# bat_mini7.net
KiCad netlist of a schematic drawn in EAGLE
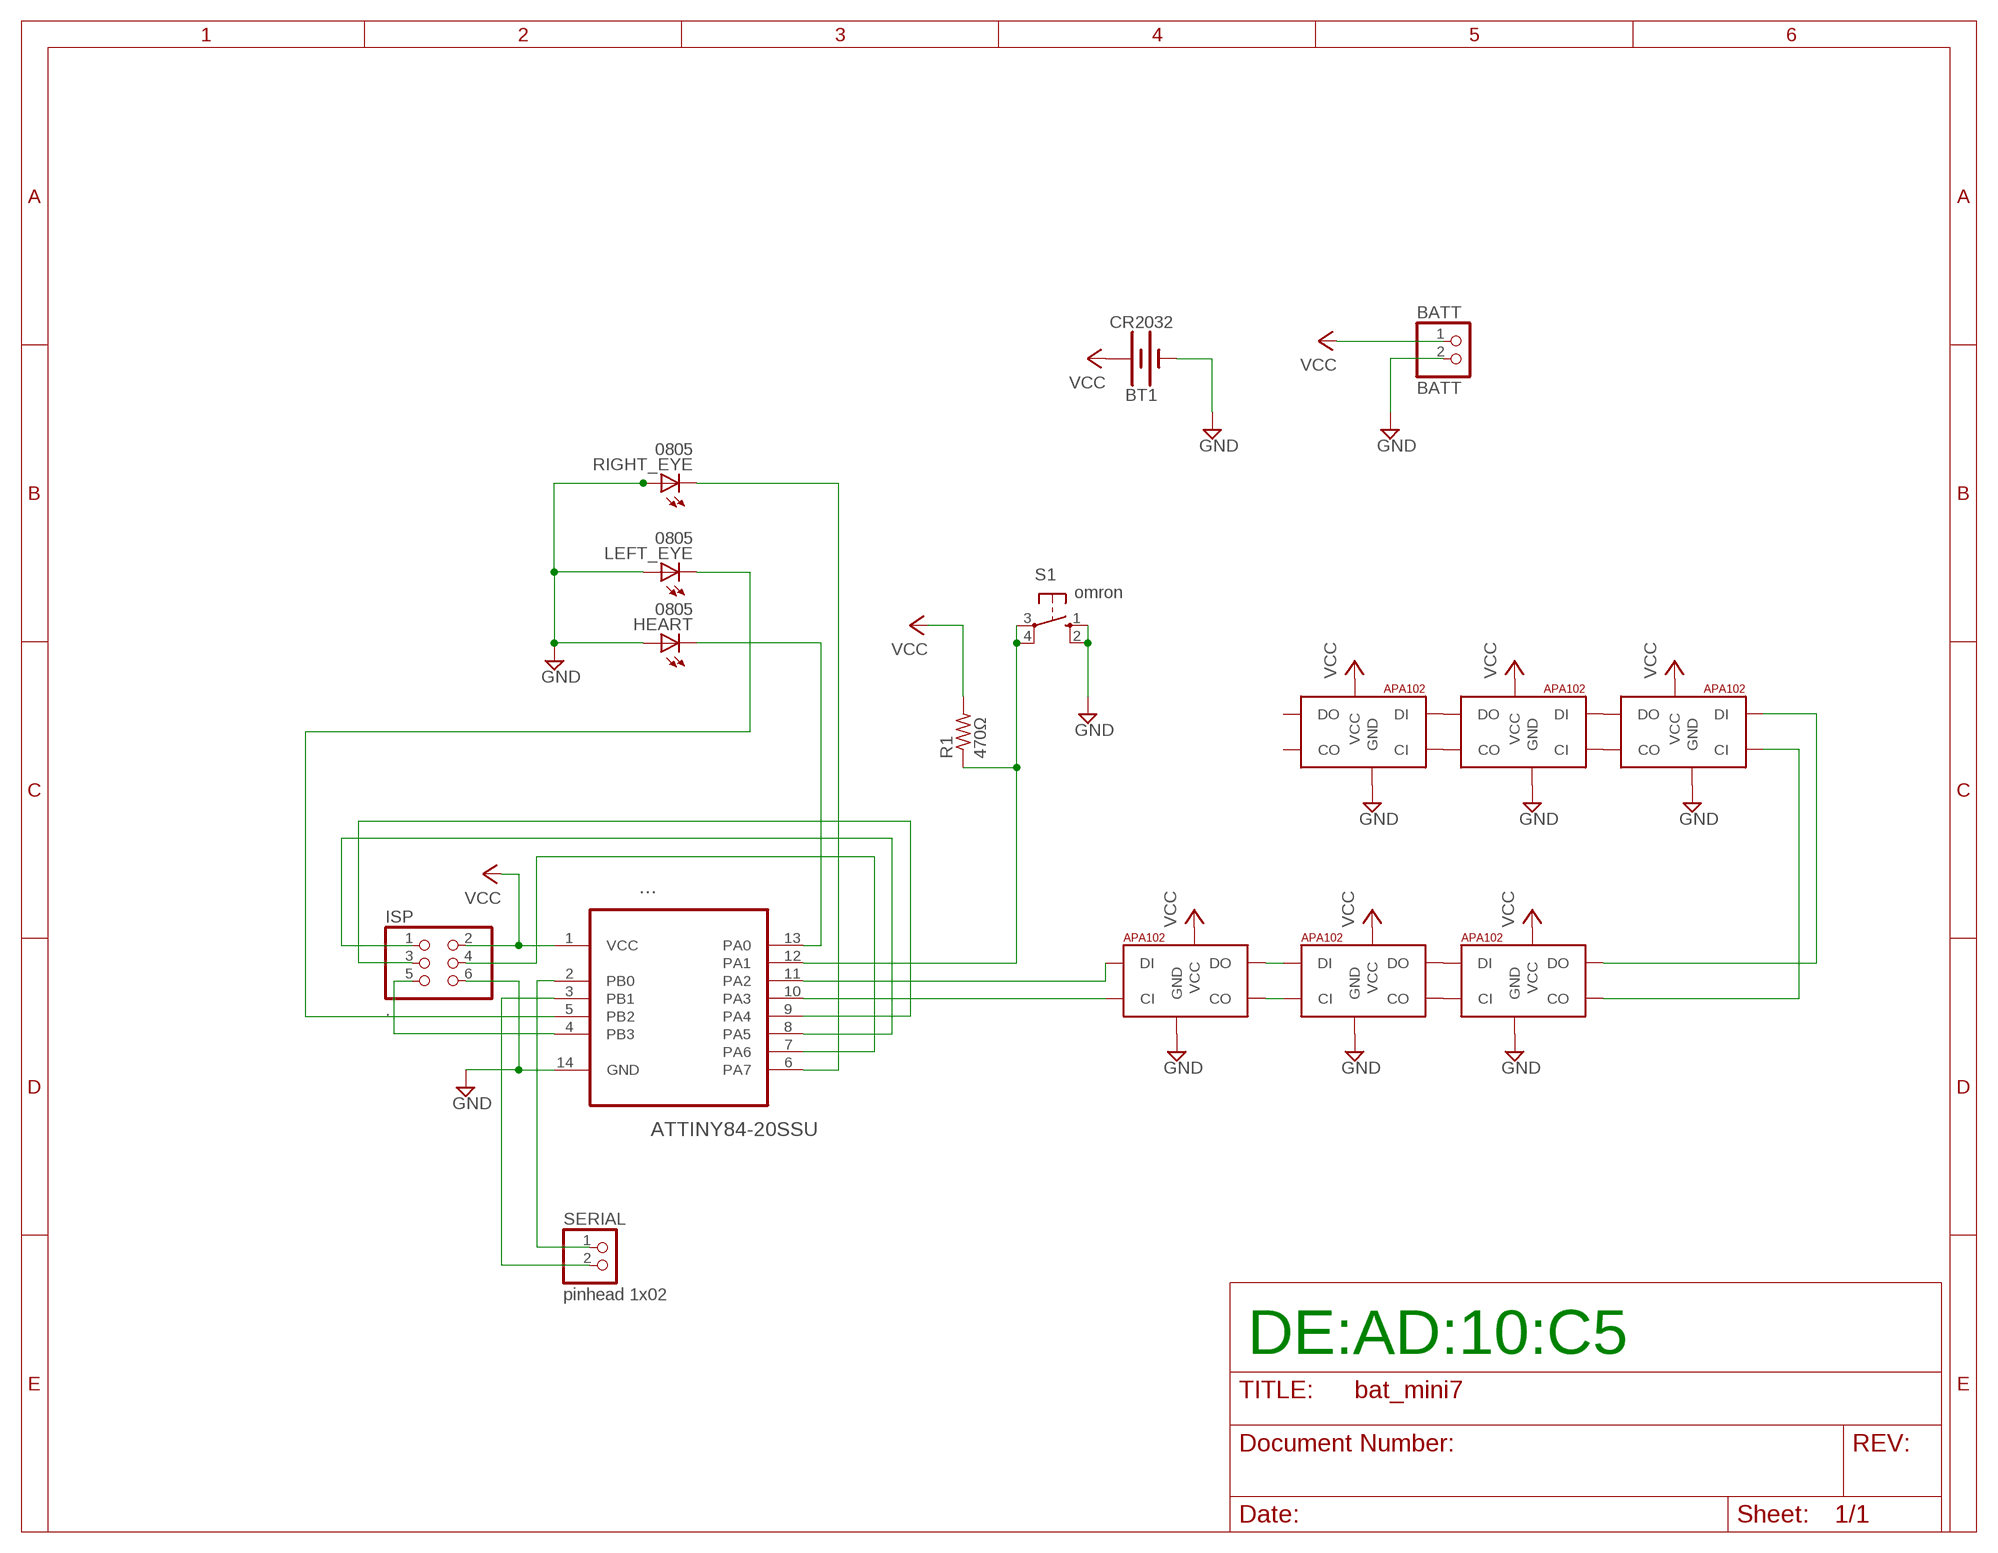
[diagram p0: schematic, sheet 1]

(export (version "E")
  (design (tool "Eeschema 10.0.6"))
  (components
    (comp (ref "...")
      (value "ATTINY84-20SSU")
      (footprint "eagle-import:SOIC127P600X175-14N")
      (libsource (lib "eagle-import") (part "ATTINY84-20SSU"))
    )
    (comp (ref "BATT")
      (value "BATT")
      (footprint "eagle-import:1X02")
      (libsource (lib "eagle-import") (part "PINHD-1X2"))
    )
    (comp (ref "BT1")
      (value "CR2032")
      (footprint "eagle-import:BATTCON_20MM_4LEGS")
      (libsource (lib "eagle-import") (part "BATTERY-20MM_SMD_4LEGS"))
    )
    (comp (ref "HEART")
      (value "0805")
      (footprint "eagle-import:CHIP-LED0805")
      (libsource (lib "eagle-import") (part "LEDCHIP-LED0805"))
    )
    (comp (ref "ISP")
      (value ".")
      (footprint "eagle-import:2X03")
      (libsource (lib "eagle-import") (part "PINHD-2X3"))
    )
    (comp (ref "LEFT_EYE")
      (value "0805")
      (footprint "eagle-import:CHIP-LED0805")
      (libsource (lib "eagle-import") (part "LEDCHIP-LED0805"))
    )
    (comp (ref "R1")
      (value "470Ω")
      (footprint "eagle-import:R0805")
      (libsource (lib "eagle-import") (part "R-US_R0805"))
    )
    (comp (ref "RIGHT_EYE")
      (value "0805")
      (footprint "eagle-import:CHIP-LED0805")
      (libsource (lib "eagle-import") (part "LEDCHIP-LED0805"))
    )
    (comp (ref "S1")
      (value "omron")
      (footprint "eagle-import:B3F-10XX")
      (fields (field (name "MPN") "B3F-1000"))
      (libsource (lib "eagle-import") (part "10-XX"))
    )
    (comp (ref "SERIAL")
      (value "pinhead 1x02")
      (footprint "eagle-import:1X02")
      (libsource (lib "eagle-import") (part "PINHD-1X2"))
    )
    (comp (ref "U$1")
      (value "APA1025050")
      (footprint "eagle-import:APA102_5050")
      (libsource (lib "eagle-import") (part "APA1025050"))
    )
    (comp (ref "U$2")
      (value "APA1025050")
      (footprint "eagle-import:APA102_5050")
      (libsource (lib "eagle-import") (part "APA1025050"))
    )
    (comp (ref "U$3")
      (value "APA1025050")
      (footprint "eagle-import:APA102_5050")
      (libsource (lib "eagle-import") (part "APA1025050"))
    )
    (comp (ref "U$5")
      (value "APA1025050")
      (footprint "eagle-import:APA102_5050")
      (libsource (lib "eagle-import") (part "APA1025050"))
    )
    (comp (ref "U$6")
      (value "APA1025050")
      (footprint "eagle-import:APA102_5050")
      (libsource (lib "eagle-import") (part "APA1025050"))
    )
    (comp (ref "U$7")
      (value "APA1025050")
      (footprint "eagle-import:APA102_5050")
      (libsource (lib "eagle-import") (part "APA1025050"))
    )
  )
  (nets
    (net (code "1") (name "GND") (class "Default")
      (node (ref "...") (pin "14") (pinfunction "GND_14") (pintype "passive"))
      (node (ref "BATT") (pin "2") (pinfunction "2_2") (pintype "passive"))
      (node (ref "BT1") (pin "NEGATIVE") (pinfunction "-_NEGATIVE") (pintype "power_in"))
      (node (ref "HEART") (pin "A") (pinfunction "A_A") (pintype "passive"))
      (node (ref "ISP") (pin "6") (pinfunction "6_6") (pintype "passive"))
      (node (ref "LEFT_EYE") (pin "A") (pinfunction "A_A") (pintype "passive"))
      (node (ref "RIGHT_EYE") (pin "A") (pinfunction "A_A") (pintype "passive"))
      (node (ref "S1") (pin "1") (pinfunction "S_1") (pintype "passive"))
      (node (ref "S1") (pin "2") (pinfunction "S1_2") (pintype "passive"))
      (node (ref "U$1") (pin "6") (pinfunction "GND_6") (pintype "bidirectional"))
      (node (ref "U$2") (pin "6") (pinfunction "GND_6") (pintype "bidirectional"))
      (node (ref "U$3") (pin "6") (pinfunction "GND_6") (pintype "bidirectional"))
      (node (ref "U$5") (pin "6") (pinfunction "GND_6") (pintype "bidirectional"))
      (node (ref "U$6") (pin "6") (pinfunction "GND_6") (pintype "bidirectional"))
      (node (ref "U$7") (pin "6") (pinfunction "GND_6") (pintype "bidirectional"))
    )
    (net (code "2") (name "Net-(...-PA0)") (class "Default")
      (node (ref "...") (pin "13") (pinfunction "PA0_13") (pintype "bidirectional"))
      (node (ref "HEART") (pin "C") (pinfunction "C_C") (pintype "passive"))
    )
    (net (code "3") (name "Net-(...-PA1)") (class "Default")
      (node (ref "...") (pin "12") (pinfunction "PA1_12") (pintype "bidirectional"))
      (node (ref "R1") (pin "1") (pinfunction "1_1") (pintype "passive"))
      (node (ref "S1") (pin "3") (pinfunction "P_3") (pintype "passive"))
      (node (ref "S1") (pin "4") (pinfunction "P1_4") (pintype "passive"))
    )
    (net (code "4") (name "Net-(...-PA2)") (class "Default")
      (node (ref "...") (pin "11") (pinfunction "PA2_11") (pintype "bidirectional"))
      (node (ref "U$1") (pin "4") (pinfunction "DI_4") (pintype "bidirectional"))
    )
    (net (code "5") (name "Net-(...-PA3)") (class "Default")
      (node (ref "...") (pin "10") (pinfunction "PA3_10") (pintype "bidirectional"))
      (node (ref "U$1") (pin "5") (pinfunction "CI_5") (pintype "bidirectional"))
    )
    (net (code "6") (name "Net-(...-PA4)") (class "Default")
      (node (ref "...") (pin "9") (pinfunction "PA4_9") (pintype "bidirectional"))
      (node (ref "ISP") (pin "3") (pinfunction "3_3") (pintype "passive"))
    )
    (net (code "7") (name "Net-(...-PA5)") (class "Default")
      (node (ref "...") (pin "8") (pinfunction "PA5_8") (pintype "bidirectional"))
      (node (ref "ISP") (pin "1") (pinfunction "1_1") (pintype "passive"))
    )
    (net (code "8") (name "Net-(...-PA6)") (class "Default")
      (node (ref "...") (pin "7") (pinfunction "PA6_7") (pintype "bidirectional"))
      (node (ref "ISP") (pin "4") (pinfunction "4_4") (pintype "passive"))
    )
    (net (code "9") (name "Net-(...-PA7)") (class "Default")
      (node (ref "...") (pin "6") (pinfunction "PA7_6") (pintype "bidirectional"))
      (node (ref "RIGHT_EYE") (pin "C") (pinfunction "C_C") (pintype "passive"))
    )
    (net (code "10") (name "Net-(...-PB0)") (class "Default")
      (node (ref "...") (pin "2") (pinfunction "PB0_2") (pintype "bidirectional"))
      (node (ref "SERIAL") (pin "1") (pinfunction "1_1") (pintype "passive"))
    )
    (net (code "11") (name "Net-(...-PB1)") (class "Default")
      (node (ref "...") (pin "3") (pinfunction "PB1_3") (pintype "bidirectional"))
      (node (ref "SERIAL") (pin "2") (pinfunction "2_2") (pintype "passive"))
    )
    (net (code "12") (name "Net-(...-PB2)") (class "Default")
      (node (ref "...") (pin "5") (pinfunction "PB2_5") (pintype "bidirectional"))
      (node (ref "LEFT_EYE") (pin "C") (pinfunction "C_C") (pintype "passive"))
    )
    (net (code "13") (name "Net-(...-PB3)") (class "Default")
      (node (ref "...") (pin "4") (pinfunction "PB3_4") (pintype "bidirectional"))
      (node (ref "ISP") (pin "5") (pinfunction "5_5") (pintype "passive"))
    )
    (net (code "14") (name "Net-(U$1-CO)") (class "Default")
      (node (ref "U$1") (pin "2") (pinfunction "CO_2") (pintype "bidirectional"))
      (node (ref "U$2") (pin "5") (pinfunction "CI_5") (pintype "bidirectional"))
    )
    (net (code "15") (name "Net-(U$1-DO)") (class "Default")
      (node (ref "U$1") (pin "3") (pinfunction "DO_3") (pintype "bidirectional"))
      (node (ref "U$2") (pin "4") (pinfunction "DI_4") (pintype "bidirectional"))
    )
    (net (code "16") (name "Net-(U$2-CO)") (class "Default")
      (node (ref "U$2") (pin "2") (pinfunction "CO_2") (pintype "bidirectional"))
      (node (ref "U$3") (pin "5") (pinfunction "CI_5") (pintype "bidirectional"))
    )
    (net (code "17") (name "Net-(U$2-DO)") (class "Default")
      (node (ref "U$2") (pin "3") (pinfunction "DO_3") (pintype "bidirectional"))
      (node (ref "U$3") (pin "4") (pinfunction "DI_4") (pintype "bidirectional"))
    )
    (net (code "18") (name "Net-(U$3-CO)") (class "Default")
      (node (ref "U$3") (pin "2") (pinfunction "CO_2") (pintype "bidirectional"))
      (node (ref "U$5") (pin "5") (pinfunction "CI_5") (pintype "bidirectional"))
    )
    (net (code "19") (name "Net-(U$3-DO)") (class "Default")
      (node (ref "U$3") (pin "3") (pinfunction "DO_3") (pintype "bidirectional"))
      (node (ref "U$5") (pin "4") (pinfunction "DI_4") (pintype "bidirectional"))
    )
    (net (code "20") (name "Net-(U$5-CO)") (class "Default")
      (node (ref "U$5") (pin "2") (pinfunction "CO_2") (pintype "bidirectional"))
      (node (ref "U$6") (pin "5") (pinfunction "CI_5") (pintype "bidirectional"))
    )
    (net (code "21") (name "Net-(U$5-DO)") (class "Default")
      (node (ref "U$5") (pin "3") (pinfunction "DO_3") (pintype "bidirectional"))
      (node (ref "U$6") (pin "4") (pinfunction "DI_4") (pintype "bidirectional"))
    )
    (net (code "22") (name "Net-(U$6-CO)") (class "Default")
      (node (ref "U$6") (pin "2") (pinfunction "CO_2") (pintype "bidirectional"))
      (node (ref "U$7") (pin "5") (pinfunction "CI_5") (pintype "bidirectional"))
    )
    (net (code "23") (name "Net-(U$6-DO)") (class "Default")
      (node (ref "U$6") (pin "3") (pinfunction "DO_3") (pintype "bidirectional"))
      (node (ref "U$7") (pin "4") (pinfunction "DI_4") (pintype "bidirectional"))
    )
    (net (code "24") (name "VCC") (class "Default")
      (node (ref "...") (pin "1") (pinfunction "VCC_1") (pintype "power_in"))
      (node (ref "BATT") (pin "1") (pinfunction "1_1") (pintype "passive"))
      (node (ref "BT1") (pin "POSITIVE@1") (pinfunction "+_POSITIVE@1") (pintype "power_in"))
      (node (ref "BT1") (pin "POSITIVE@2") (pinfunction "+_POSITIVE@2") (pintype "power_in"))
      (node (ref "BT1") (pin "POSITIVE@3") (pinfunction "+_POSITIVE@3") (pintype "power_in"))
      (node (ref "BT1") (pin "POSITIVE@4") (pinfunction "+_POSITIVE@4") (pintype "power_in"))
      (node (ref "ISP") (pin "2") (pinfunction "2_2") (pintype "passive"))
      (node (ref "R1") (pin "2") (pinfunction "2_2") (pintype "passive"))
      (node (ref "U$1") (pin "1") (pinfunction "VCC_1") (pintype "bidirectional"))
      (node (ref "U$2") (pin "1") (pinfunction "VCC_1") (pintype "bidirectional"))
      (node (ref "U$3") (pin "1") (pinfunction "VCC_1") (pintype "bidirectional"))
      (node (ref "U$5") (pin "1") (pinfunction "VCC_1") (pintype "bidirectional"))
      (node (ref "U$6") (pin "1") (pinfunction "VCC_1") (pintype "bidirectional"))
      (node (ref "U$7") (pin "1") (pinfunction "VCC_1") (pintype "bidirectional"))
    )
    (net (code "25") (name "unconnected-(U$7-CO-Pad2)") (class "Default")
      (node (ref "U$7") (pin "2") (pinfunction "CO_2") (pintype "bidirectional"))
    )
    (net (code "26") (name "unconnected-(U$7-DO-Pad3)") (class "Default")
      (node (ref "U$7") (pin "3") (pinfunction "DO_3") (pintype "bidirectional"))
    )
  )
)
